# DRV8411A_Module_Rev_A.net
KiCad netlist of a schematic drawn in EAGLE
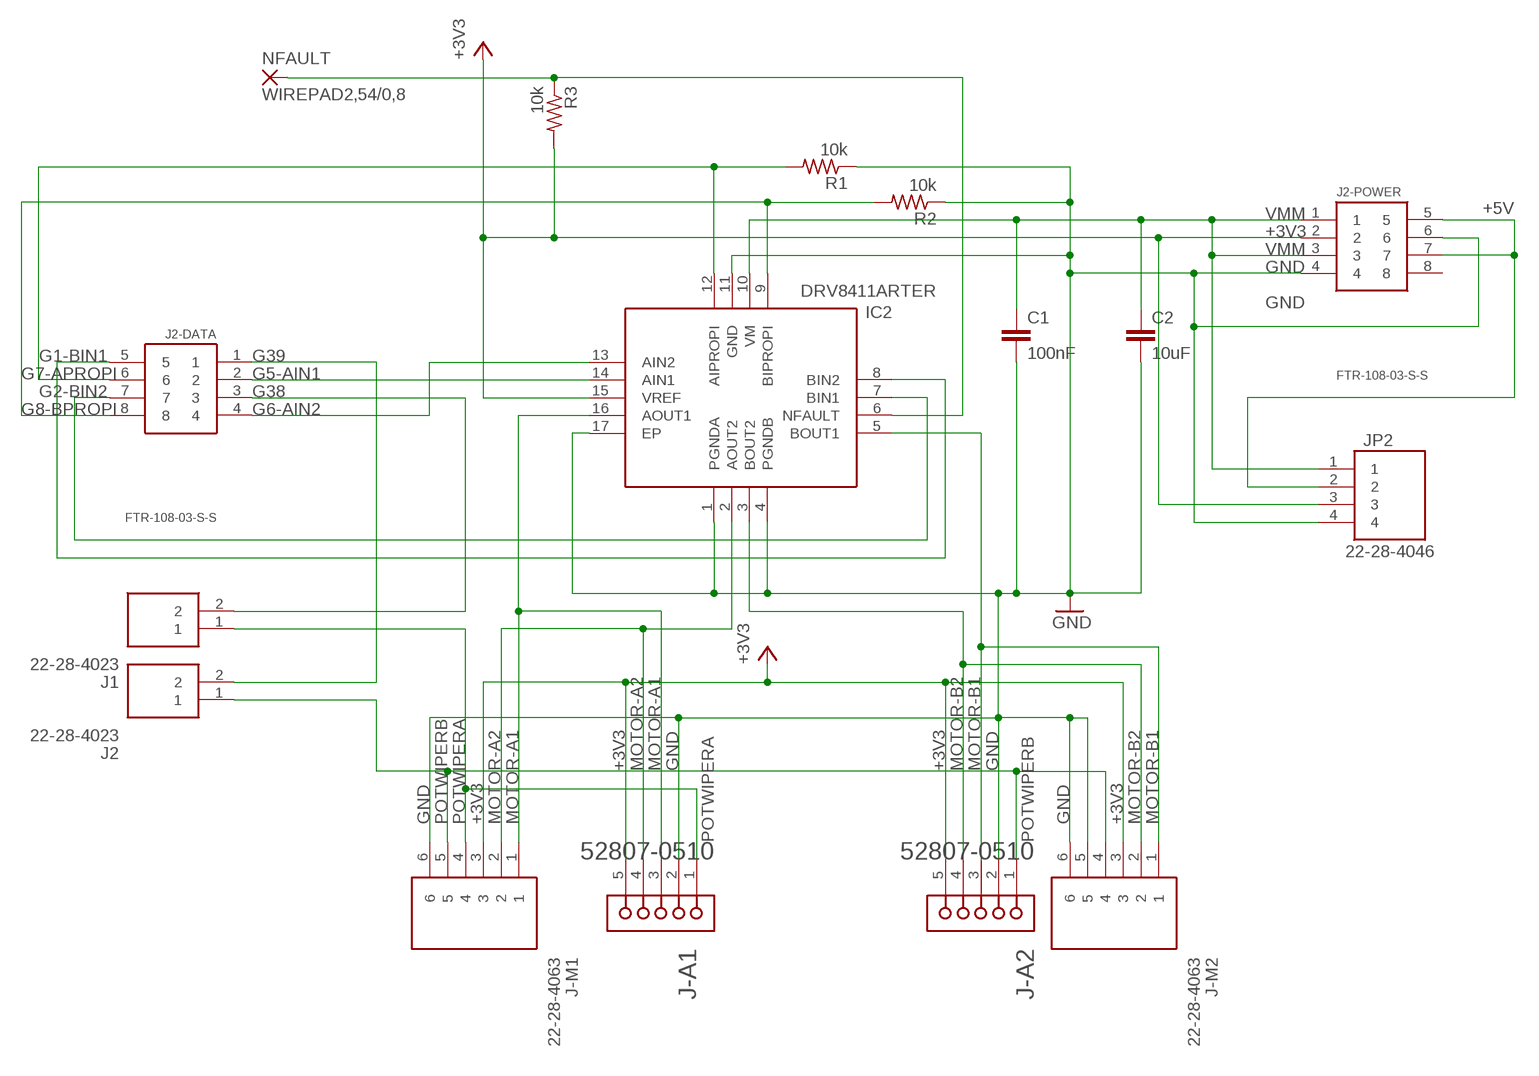
[diagram p0: schematic, sheet 1]

(export (version "E")
  (design (tool "Eeschema 10.0.6"))
  (components
    (comp (ref "C1")
      (value "100nF")
      (footprint "eagle-import:C0603")
      (libsource (lib "eagle-import") (part "C-EUC0603"))
    )
    (comp (ref "C2")
      (value "10uF")
      (footprint "eagle-import:C1206")
      (libsource (lib "eagle-import") (part "C-EUC1206"))
    )
    (comp (ref "IC2")
      (value "DRV8411ARTER")
      (footprint "eagle-import:QFN50P300X300X80-17N")
      (fields (field (name "MOUSER_PART_NUMBER") "595-DRV8411ARTER"))
      (libsource (lib "eagle-import") (part "DRV8411ARTER"))
    )
    (comp (ref "J-A1")
      (value "MOLEX_52807-0510MOLEX_52807-0510_0_0")
      (footprint "eagle-import:MOLEX_52807-0510_0")
      (fields (field (name "MF") "Molex") (field (name "MPN") "52807-0510"))
      (libsource (lib "eagle-import") (part "MOLEX_52807-0510MOLEX_52807-0510_0_0"))
    )
    (comp (ref "J-A2")
      (value "MOLEX_52807-0510MOLEX_52807-0510_0_0")
      (footprint "eagle-import:MOLEX_52807-0510_0")
      (fields (field (name "MF") "Molex") (field (name "MPN") "52807-0510"))
      (libsource (lib "eagle-import") (part "MOLEX_52807-0510MOLEX_52807-0510_0_0"))
    )
    (comp (ref "J-M1")
      (value "22-28-4063")
      (footprint "eagle-import:HDRV6W66P0X254_1X6_1524X249X83")
      (fields (field (name "MOUSER_PART_NUMBER") "538-22-28-4063"))
      (libsource (lib "eagle-import") (part "22-28-4063"))
    )
    (comp (ref "J-M2")
      (value "22-28-4063")
      (footprint "eagle-import:HDRV6W66P0X254_1X6_1524X249X83")
      (fields (field (name "MOUSER_PART_NUMBER") "538-22-28-4063"))
      (libsource (lib "eagle-import") (part "22-28-4063"))
    )
    (comp (ref "J1")
      (value "22-28-4023")
      (footprint "eagle-import:HDRV2W87P0X254_1X2_508X249X863")
      (fields (field (name "MOUSER_PART_NUMBER") "538-22-28-4023"))
      (libsource (lib "eagle-import") (part "22-28-4023"))
    )
    (comp (ref "J2")
      (value "22-28-4023")
      (footprint "eagle-import:HDRV2W87P0X254_1X2_508X249X863")
      (fields (field (name "MOUSER_PART_NUMBER") "538-22-28-4023"))
      (libsource (lib "eagle-import") (part "22-28-4023"))
    )
    (comp (ref "J2-DATA")
      (value "FTR-108-03-S-S")
      (footprint "eagle-import:HUSRSP8W46P127_1016X248X572P")
      (libsource (lib "eagle-import") (part "FTR-108-03-S-S"))
    )
    (comp (ref "J2-POWER")
      (value "FTR-108-03-S-S")
      (footprint "eagle-import:HUSRSP8W46P127_1016X248X572P")
      (libsource (lib "eagle-import") (part "FTR-108-03-S-S"))
    )
    (comp (ref "JP2")
      (value "22-28-4046")
      (footprint "eagle-import:HDRV4W66P0X254_1X4_1016X249X83")
      (fields (field (name "MOUSER_PART_NUMBER") "538-22-28-4046"))
      (libsource (lib "eagle-import") (part "22-28-4046"))
    )
    (comp (ref "NFAULT")
      (value "WIREPAD2,54/0,8")
      (footprint "eagle-import:2,54_0,8")
      (libsource (lib "eagle-import") (part "WIREPAD2,54/0,8"))
    )
    (comp (ref "R1")
      (value "10k")
      (footprint "eagle-import:R1206")
      (libsource (lib "eagle-import") (part "R-US_R1206"))
    )
    (comp (ref "R2")
      (value "10k")
      (footprint "eagle-import:R1206")
      (libsource (lib "eagle-import") (part "R-US_R1206"))
    )
    (comp (ref "R3")
      (value "10k")
      (footprint "eagle-import:R1206")
      (libsource (lib "eagle-import") (part "R-US_R1206"))
    )
  )
  (nets
    (net (code "1") (name "+3V3") (class "Default")
      (node (ref "IC2") (pin "15") (pinfunction "VREF_15") (pintype "bidirectional"))
      (node (ref "J-A1") (pin "5") (pinfunction "5_5") (pintype "passive"))
      (node (ref "J-A2") (pin "5") (pinfunction "5_5") (pintype "passive"))
      (node (ref "J-M1") (pin "3") (pinfunction "3_3") (pintype "bidirectional"))
      (node (ref "J-M2") (pin "3") (pinfunction "3_3") (pintype "bidirectional"))
      (node (ref "J2-POWER") (pin "2") (pinfunction "2_2") (pintype "bidirectional"))
      (node (ref "JP2") (pin "3") (pinfunction "3_3") (pintype "bidirectional"))
      (node (ref "R3") (pin "2") (pinfunction "2_2") (pintype "passive"))
    )
    (net (code "2") (name "/+5V") (class "Default")
      (node (ref "J2-POWER") (pin "5") (pinfunction "5_5") (pintype "bidirectional"))
      (node (ref "J2-POWER") (pin "7") (pinfunction "7_7") (pintype "bidirectional"))
      (node (ref "JP2") (pin "2") (pinfunction "2_2") (pintype "bidirectional"))
    )
    (net (code "3") (name "/G1-BIN1") (class "Default")
      (node (ref "IC2") (pin "8") (pinfunction "BIN2_8") (pintype "bidirectional"))
      (node (ref "J2-DATA") (pin "5") (pinfunction "5_5") (pintype "bidirectional"))
    )
    (net (code "4") (name "/G2-BIN2") (class "Default")
      (node (ref "IC2") (pin "7") (pinfunction "BIN1_7") (pintype "bidirectional"))
      (node (ref "J2-DATA") (pin "7") (pinfunction "7_7") (pintype "bidirectional"))
    )
    (net (code "5") (name "/G5-AIN1") (class "Default")
      (node (ref "IC2") (pin "14") (pinfunction "AIN1_14") (pintype "bidirectional"))
      (node (ref "J2-DATA") (pin "2") (pinfunction "2_2") (pintype "bidirectional"))
    )
    (net (code "6") (name "/G6-AIN2") (class "Default")
      (node (ref "IC2") (pin "13") (pinfunction "AIN2_13") (pintype "bidirectional"))
      (node (ref "J2-DATA") (pin "4") (pinfunction "4_4") (pintype "bidirectional"))
    )
    (net (code "7") (name "/G7-APROPI") (class "Default")
      (node (ref "IC2") (pin "12") (pinfunction "AIPROPI_12") (pintype "bidirectional"))
      (node (ref "J2-DATA") (pin "6") (pinfunction "6_6") (pintype "bidirectional"))
      (node (ref "R1") (pin "2") (pinfunction "2_2") (pintype "passive"))
    )
    (net (code "8") (name "/G8-BPROPI") (class "Default")
      (node (ref "IC2") (pin "9") (pinfunction "BIPROPI_9") (pintype "bidirectional"))
      (node (ref "J2-DATA") (pin "8") (pinfunction "8_8") (pintype "bidirectional"))
      (node (ref "R2") (pin "2") (pinfunction "2_2") (pintype "passive"))
    )
    (net (code "9") (name "/G38") (class "Default")
      (node (ref "J1") (pin "2") (pinfunction "2_2") (pintype "bidirectional"))
      (node (ref "J2-DATA") (pin "3") (pinfunction "3_3") (pintype "bidirectional"))
    )
    (net (code "10") (name "/G39") (class "Default")
      (node (ref "J2") (pin "2") (pinfunction "2_2") (pintype "bidirectional"))
      (node (ref "J2-DATA") (pin "1") (pinfunction "1_1") (pintype "bidirectional"))
    )
    (net (code "11") (name "/MOTOR-A1") (class "Default")
      (node (ref "IC2") (pin "16") (pinfunction "AOUT1_16") (pintype "bidirectional"))
      (node (ref "J-A1") (pin "3") (pinfunction "3_3") (pintype "passive"))
      (node (ref "J-M1") (pin "1") (pinfunction "1_1") (pintype "bidirectional"))
    )
    (net (code "12") (name "/MOTOR-A2") (class "Default")
      (node (ref "IC2") (pin "2") (pinfunction "AOUT2_2") (pintype "bidirectional"))
      (node (ref "J-A1") (pin "4") (pinfunction "4_4") (pintype "passive"))
      (node (ref "J-M1") (pin "2") (pinfunction "2_2") (pintype "bidirectional"))
    )
    (net (code "13") (name "/MOTOR-B1") (class "Default")
      (node (ref "IC2") (pin "5") (pinfunction "BOUT1_5") (pintype "bidirectional"))
      (node (ref "J-A2") (pin "3") (pinfunction "3_3") (pintype "passive"))
      (node (ref "J-M2") (pin "1") (pinfunction "1_1") (pintype "bidirectional"))
    )
    (net (code "14") (name "/MOTOR-B2") (class "Default")
      (node (ref "IC2") (pin "3") (pinfunction "BOUT2_3") (pintype "bidirectional"))
      (node (ref "J-A2") (pin "4") (pinfunction "4_4") (pintype "passive"))
      (node (ref "J-M2") (pin "2") (pinfunction "2_2") (pintype "bidirectional"))
    )
    (net (code "15") (name "/POTWIPERA") (class "Default")
      (node (ref "J-A1") (pin "1") (pinfunction "1_1") (pintype "passive"))
      (node (ref "J-M1") (pin "4") (pinfunction "4_4") (pintype "bidirectional"))
      (node (ref "J1") (pin "1") (pinfunction "1_1") (pintype "bidirectional"))
    )
    (net (code "16") (name "/POTWIPERB") (class "Default")
      (node (ref "J-A2") (pin "1") (pinfunction "1_1") (pintype "passive"))
      (node (ref "J-M1") (pin "5") (pinfunction "5_5") (pintype "bidirectional"))
      (node (ref "J-M2") (pin "4") (pinfunction "4_4") (pintype "bidirectional"))
      (node (ref "J2") (pin "1") (pinfunction "1_1") (pintype "bidirectional"))
    )
    (net (code "17") (name "/VMM") (class "Default")
      (node (ref "C1") (pin "1") (pinfunction "1_1") (pintype "passive"))
      (node (ref "C2") (pin "1") (pinfunction "1_1") (pintype "passive"))
      (node (ref "IC2") (pin "10") (pinfunction "VM_10") (pintype "bidirectional"))
      (node (ref "J2-POWER") (pin "1") (pinfunction "1_1") (pintype "bidirectional"))
      (node (ref "J2-POWER") (pin "3") (pinfunction "3_3") (pintype "bidirectional"))
      (node (ref "JP2") (pin "1") (pinfunction "1_1") (pintype "bidirectional"))
    )
    (net (code "18") (name "GND") (class "Default")
      (node (ref "C1") (pin "2") (pinfunction "2_2") (pintype "passive"))
      (node (ref "C2") (pin "2") (pinfunction "2_2") (pintype "passive"))
      (node (ref "IC2") (pin "1") (pinfunction "PGNDA_1") (pintype "bidirectional"))
      (node (ref "IC2") (pin "11") (pinfunction "GND_11") (pintype "bidirectional"))
      (node (ref "IC2") (pin "17") (pinfunction "EP_17") (pintype "bidirectional"))
      (node (ref "IC2") (pin "4") (pinfunction "PGNDB_4") (pintype "bidirectional"))
      (node (ref "J-A1") (pin "2") (pinfunction "2_2") (pintype "passive"))
      (node (ref "J-A2") (pin "2") (pinfunction "2_2") (pintype "passive"))
      (node (ref "J-M1") (pin "6") (pinfunction "6_6") (pintype "bidirectional"))
      (node (ref "J-M2") (pin "5") (pinfunction "5_5") (pintype "bidirectional"))
      (node (ref "J-M2") (pin "6") (pinfunction "6_6") (pintype "bidirectional"))
      (node (ref "J2-POWER") (pin "4") (pinfunction "4_4") (pintype "bidirectional"))
      (node (ref "J2-POWER") (pin "6") (pinfunction "6_6") (pintype "bidirectional"))
      (node (ref "JP2") (pin "4") (pinfunction "4_4") (pintype "bidirectional"))
      (node (ref "R1") (pin "1") (pinfunction "1_1") (pintype "passive"))
      (node (ref "R2") (pin "1") (pinfunction "1_1") (pintype "passive"))
    )
    (net (code "19") (name "Net-(IC2-NFAULT)") (class "Default")
      (node (ref "IC2") (pin "6") (pinfunction "NFAULT_6") (pintype "bidirectional"))
      (node (ref "NFAULT") (pin "1") (pinfunction "P_1") (pintype "passive"))
      (node (ref "R3") (pin "1") (pinfunction "1_1") (pintype "passive"))
    )
    (net (code "20") (name "unconnected-(J2-POWER-Pad8)") (class "Default")
      (node (ref "J2-POWER") (pin "8") (pinfunction "8_8") (pintype "bidirectional"))
    )
  )
)
